# POWER.net
KiCad netlist of a schematic drawn in Altium Designer
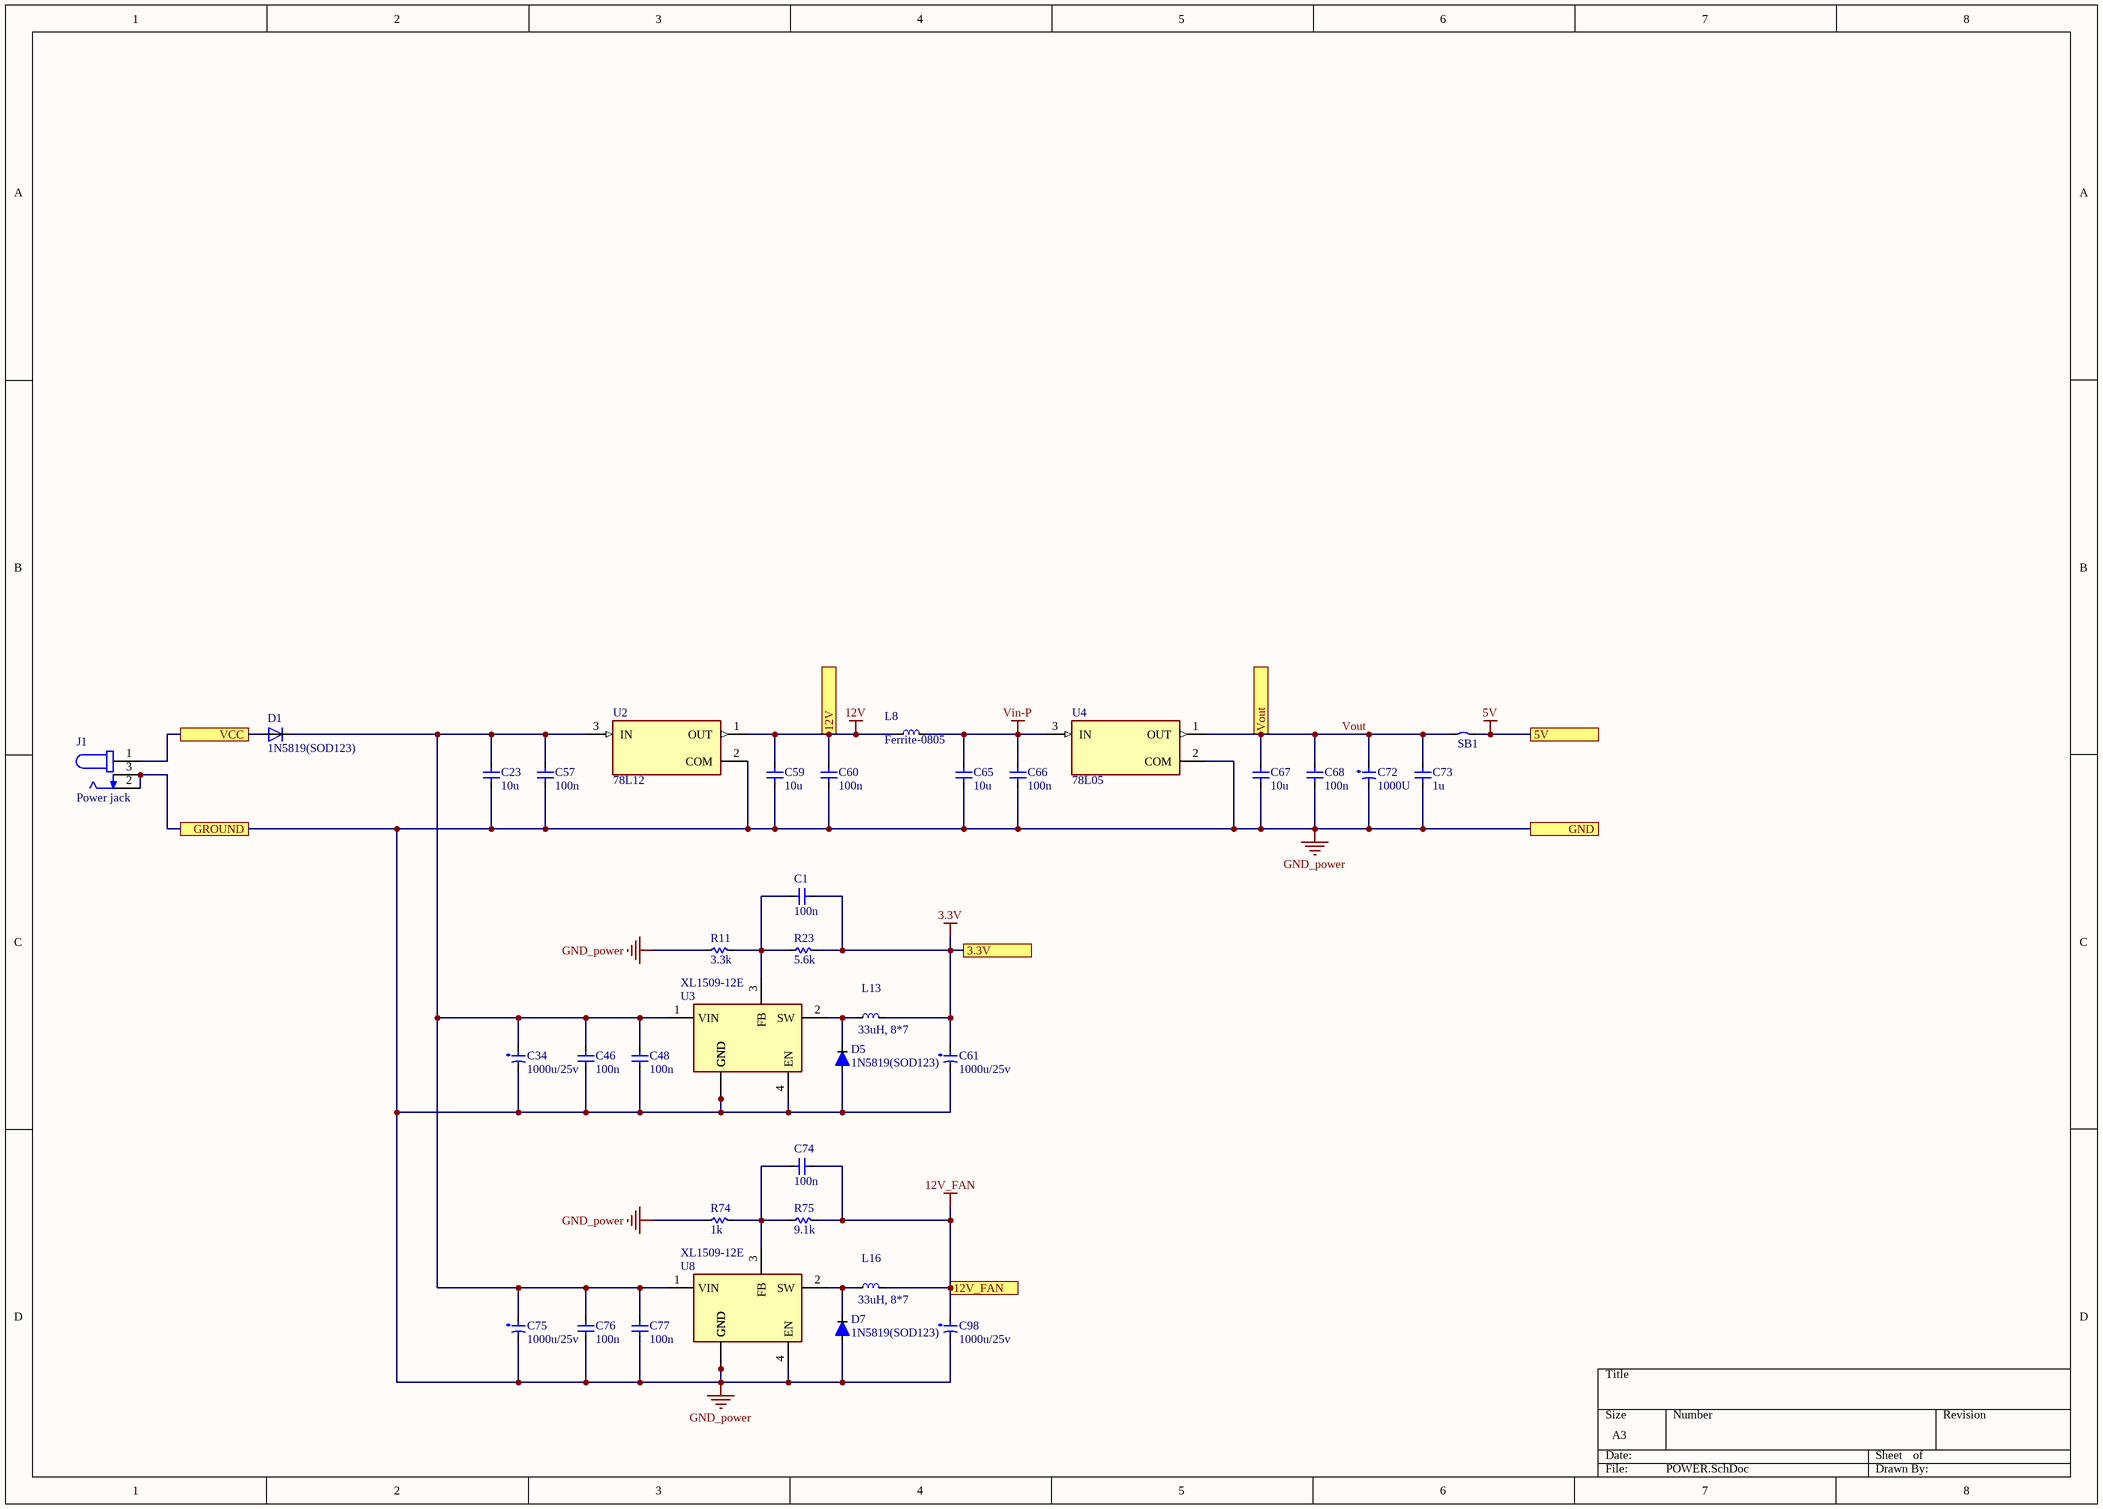
[diagram p0: POWER.SchDoc]

(export (version "E")
  (design (tool "Eeschema 10.0.6"))
  (components
    (comp (ref "C1")
      (value "100n")
      (footprint "cap0603")
      (description "Capacitor 0603")
      (fields (field (name "PUBLISHER") "Altium Limited"))
      (libsource (lib "STM32F103C8T6") (part "Cap 0603"))
    )
    (comp (ref "C23")
      (value "10u")
      (footprint "CAP 0805")
      (description "Capacitor 0805")
      (fields (field (name "PUBLISHER") "Altium Limited"))
      (libsource (lib "Amin-Library") (part "Cap 0805"))
    )
    (comp (ref "C34")
      (value "1000u/25v")
      (footprint "CAP DIP 10*13")
      (description "2200ÂµF 50V Aluminum Electrolytic Capacitors Radial, Can 1000 Hrs @ 105Â°C")
      (fields (field (name "MF") "Nichicon") (field (name "MP") "UVZ1H222MHD"))
      (libsource (lib "mylib1") (part "capacitor dip 10*13"))
    )
    (comp (ref "C46")
      (value "100n")
      (footprint "cap0603")
      (description "Capacitor 0603")
      (fields (field (name "PUBLISHER") "Altium Limited"))
      (libsource (lib "STM32F103C8T6") (part "Cap 0603"))
    )
    (comp (ref "C48")
      (value "100n")
      (footprint "cap0603")
      (description "Capacitor 0603")
      (fields (field (name "PUBLISHER") "Altium Limited"))
      (libsource (lib "STM32F103C8T6") (part "Cap 0603"))
    )
    (comp (ref "C57")
      (value "100n")
      (footprint "cap0603")
      (description "Capacitor 0603")
      (fields (field (name "PUBLISHER") "Altium Limited"))
      (libsource (lib "STM32F103C8T6") (part "Cap 0603"))
    )
    (comp (ref "C59")
      (value "10u")
      (footprint "CAP 0805")
      (description "Capacitor 0805")
      (fields (field (name "PUBLISHER") "Altium Limited"))
      (libsource (lib "Amin-Library") (part "Cap 0805"))
    )
    (comp (ref "C60")
      (value "100n")
      (footprint "cap0603")
      (description "Capacitor 0603")
      (fields (field (name "PUBLISHER") "Altium Limited"))
      (libsource (lib "STM32F103C8T6") (part "Cap 0603"))
    )
    (comp (ref "C61")
      (value "1000u/25v")
      (footprint "CAP DIP 10*13")
      (description "2200ÂµF 50V Aluminum Electrolytic Capacitors Radial, Can 1000 Hrs @ 105Â°C")
      (fields (field (name "MF") "Nichicon") (field (name "MP") "UVZ1H222MHD"))
      (libsource (lib "mylib1") (part "capacitor dip 10*13"))
    )
    (comp (ref "C65")
      (value "10u")
      (footprint "CAP 0805")
      (description "Capacitor 0805")
      (fields (field (name "PUBLISHER") "Altium Limited"))
      (libsource (lib "Amin-Library") (part "Cap 0805"))
    )
    (comp (ref "C66")
      (value "100n")
      (footprint "cap0603")
      (description "Capacitor 0603")
      (fields (field (name "PUBLISHER") "Altium Limited"))
      (libsource (lib "STM32F103C8T6") (part "Cap 0603"))
    )
    (comp (ref "C67")
      (value "10u")
      (footprint "CAP 0805")
      (description "Capacitor 0805")
      (fields (field (name "PUBLISHER") "Altium Limited"))
      (libsource (lib "Amin-Library") (part "Cap 0805"))
    )
    (comp (ref "C68")
      (value "100n")
      (footprint "cap0603")
      (description "Capacitor 0603")
      (fields (field (name "PUBLISHER") "Altium Limited"))
      (libsource (lib "STM32F103C8T6") (part "Cap 0603"))
    )
    (comp (ref "C72")
      (value "1000U")
      (footprint "cap  dip 10*20")
      (description "2200ÂµF 50V Aluminum Electrolytic Capacitors Radial, Can 1000 Hrs @ 105Â°C")
      (fields (field (name "MF") "Nichicon") (field (name "MP") "UVZ1H222MHD"))
      (libsource (lib "Parsa-Library") (part "capacitor dip 10*20"))
    )
    (comp (ref "C73")
      (value "1u")
      (footprint "cap0603")
      (description "Capacitor 0603")
      (fields (field (name "PUBLISHER") "Altium Limited"))
      (libsource (lib "mylib") (part "Cap 0603"))
    )
    (comp (ref "C74")
      (value "100n")
      (footprint "cap0603")
      (description "Capacitor 0603")
      (fields (field (name "PUBLISHER") "Altium Limited"))
      (libsource (lib "STM32F103C8T6") (part "Cap 0603"))
    )
    (comp (ref "C75")
      (value "1000u/25v")
      (footprint "CAP DIP 10*13")
      (description "2200ÂµF 50V Aluminum Electrolytic Capacitors Radial, Can 1000 Hrs @ 105Â°C")
      (fields (field (name "MF") "Nichicon") (field (name "MP") "UVZ1H222MHD"))
      (libsource (lib "mylib1") (part "capacitor dip 10*13"))
    )
    (comp (ref "C76")
      (value "100n")
      (footprint "cap0603")
      (description "Capacitor 0603")
      (fields (field (name "PUBLISHER") "Altium Limited"))
      (libsource (lib "STM32F103C8T6") (part "Cap 0603"))
    )
    (comp (ref "C77")
      (value "100n")
      (footprint "cap0603")
      (description "Capacitor 0603")
      (fields (field (name "PUBLISHER") "Altium Limited"))
      (libsource (lib "STM32F103C8T6") (part "Cap 0603"))
    )
    (comp (ref "C98")
      (value "1000u/25v")
      (footprint "CAP DIP 10*13")
      (description "2200ÂµF 50V Aluminum Electrolytic Capacitors Radial, Can 1000 Hrs @ 105Â°C")
      (fields (field (name "MF") "Nichicon") (field (name "MP") "UVZ1H222MHD"))
      (libsource (lib "mylib1") (part "capacitor dip 10*13"))
    )
    (comp (ref "D1")
      (value "1N5819(SOD123)")
      (footprint "1N5819 SOD-123")
      (description "Shotkey diod SOD-123")
      (fields (field (name "MP") "BAS716") (field (name "MF") "Nexperia USA"))
      (libsource (lib "Amin-Library") (part "1N5819(SOD123)"))
    )
    (comp (ref "D5")
      (value "1N5819(SOD123)")
      (footprint "1N5819 SOD-123")
      (description "Shotkey diod SOD-123")
      (fields (field (name "MP") "BAS716") (field (name "MF") "Nexperia USA"))
      (libsource (lib "") (part "1N5819(SOD123)_1"))
    )
    (comp (ref "D7")
      (value "1N5819(SOD123)")
      (footprint "1N5819 SOD-123")
      (description "Shotkey diod SOD-123")
      (fields (field (name "MP") "BAS716") (field (name "MF") "Nexperia USA"))
      (libsource (lib "") (part "1N5819(SOD123)_1"))
    )
    (comp (ref "J1")
      (value "Power jack")
      (footprint "Power jack")
      (description "2.0 x 6.5 mm, 2.5 A, Horizontal, Through Hole, Tapered Pins, Dc Power Jack Connector")
      (fields (field (name "MF") "CUI Devices") (field (name "MP") "PJ-102A"))
      (libsource (lib "Amin-Library") (part "Power jack"))
    )
    (comp (ref "L8")
      (value "Ferrite-0805")
      (footprint "Ferrite-0805")
      (description "BLM Series 0805 330 Ohm 400 mA 0.58 Ohm DCR Surface Mount Ferrite Bead")
      (fields (field (name "MF") "Murata") (field (name "MP") "BLM18BB331SN1D"))
      (libsource (lib "mylib") (part "Ferrite _0805"))
    )
    (comp (ref "L13")
      (value "33uH, 8*7")
      (footprint "Inductor 8*7")
      (description "Inductor round 8*7")
      (fields (field (name "MP") "DR127-330-R") (field (name "MF") "Eaton"))
      (libsource (lib "Amin-Library") (part "INDUCTOR 8*7"))
    )
    (comp (ref "L16")
      (value "33uH, 8*7")
      (footprint "Inductor 8*7")
      (description "Inductor round 8*7")
      (fields (field (name "MP") "DR127-330-R") (field (name "MF") "Eaton"))
      (libsource (lib "Amin-Library") (part "INDUCTOR 8*7"))
    )
    (comp (ref "R11")
      (value "3.3k")
      (footprint "RES-0603")
      (description "Resistor 0603")
      (fields (field (name "PUBLISHER") "Altium Limited"))
      (libsource (lib "Amin-Library") (part "Res 0603"))
    )
    (comp (ref "R23")
      (value "5.6k")
      (footprint "RES-0603")
      (description "Resistor 0603")
      (fields (field (name "PUBLISHER") "Altium Limited"))
      (libsource (lib "Amin-Library") (part "Res 0603"))
    )
    (comp (ref "R74")
      (value "1k")
      (footprint "RES-0603")
      (description "Resistor 0603")
      (fields (field (name "PUBLISHER") "Altium Limited"))
      (libsource (lib "Amin-Library") (part "Res 0603"))
    )
    (comp (ref "R75")
      (value "9.1k")
      (footprint "RES-0603")
      (description "Resistor 0603")
      (fields (field (name "PUBLISHER") "Altium Limited"))
      (libsource (lib "Amin-Library") (part "Res 0603"))
    )
    (comp (ref "SB1")
      (value "jumper")
      (footprint "JP2_SMD")
      (description "Circuit Breaker")
      (libsource (lib "Amin-Library") (part "jumper"))
    )
    (comp (ref "U2")
      (value "78L12")
      (footprint "78L05")
      (description "Linear Voltage Regulator IC 1 Output 100mA SOT-89-3")
      (fields (field (name "MP") "UA78L05CPK") (field (name "MF") "Texas Instruments"))
      (libsource (lib "Amin-Library") (part "78L05"))
    )
    (comp (ref "U3")
      (value "XL1509-12E")
      (footprint "FR9886")
      (description "Regulator SOP-8")
      (fields (field (name "MANUFACTURER_PART_NUMBER") "FR9886SOGTR"))
      (libsource (lib "Amin-Library") (part "XL1509-12E"))
    )
    (comp (ref "U4")
      (value "78L05")
      (footprint "78L05")
      (description "Linear Voltage Regulator IC 1 Output 100mA SOT-89-3")
      (fields (field (name "MP") "UA78L05CPK") (field (name "MF") "Texas Instruments"))
      (libsource (lib "Amin-Library") (part "78L05"))
    )
    (comp (ref "U8")
      (value "XL1509-12E")
      (footprint "FR9886")
      (description "Regulator SOP-8")
      (fields (field (name "MANUFACTURER_PART_NUMBER") "FR9886SOGTR"))
      (libsource (lib "Amin-Library") (part "XL1509-12E"))
    )
  )
  (nets
    (net (code "1") (name "/VCC") (class "Default")
      (node (ref "D1") (pin "2") (pinfunction "A_2") (pintype "passive"))
      (node (ref "J1") (pin "1") (pinfunction "1_1") (pintype "passive"))
    )
    (net (code "2") (name "/Vout") (class "Default")
      (node (ref "C67") (pin "2") (pinfunction "2_2") (pintype "passive"))
      (node (ref "C68") (pin "2") (pinfunction "2_2") (pintype "passive"))
      (node (ref "C72") (pin "1") (pinfunction "POS_1") (pintype "passive"))
      (node (ref "C73") (pin "2") (pinfunction "2_2") (pintype "passive"))
      (node (ref "SB1") (pin "1") (pinfunction "1_1") (pintype "passive"))
      (node (ref "U4") (pin "1") (pinfunction "OUT_1") (pintype "output"))
    )
    (net (code "3") (name "3.3V") (class "Default")
      (node (ref "C1") (pin "1") (pinfunction "1_1") (pintype "passive"))
      (node (ref "C61") (pin "1") (pinfunction "POS_1") (pintype "passive"))
      (node (ref "L13") (pin "1") (pinfunction "1_1") (pintype "passive"))
      (node (ref "R23") (pin "2") (pinfunction "2_2") (pintype "passive"))
    )
    (net (code "4") (name "5V") (class "Default")
      (node (ref "SB1") (pin "2") (pinfunction "2_2") (pintype "passive"))
    )
    (net (code "5") (name "12V") (class "Default")
      (node (ref "C59") (pin "2") (pinfunction "2_2") (pintype "passive"))
      (node (ref "C60") (pin "2") (pinfunction "2_2") (pintype "passive"))
      (node (ref "L8") (pin "2") (pinfunction "2_2") (pintype "passive"))
      (node (ref "U2") (pin "1") (pinfunction "OUT_1") (pintype "output"))
    )
    (net (code "6") (name "12V_FAN") (class "Default")
      (node (ref "C74") (pin "1") (pinfunction "1_1") (pintype "passive"))
      (node (ref "C98") (pin "1") (pinfunction "POS_1") (pintype "passive"))
      (node (ref "L16") (pin "1") (pinfunction "1_1") (pintype "passive"))
      (node (ref "R75") (pin "2") (pinfunction "2_2") (pintype "passive"))
    )
    (net (code "7") (name "GND_power") (class "Default")
      (node (ref "C23") (pin "1") (pinfunction "1_1") (pintype "passive"))
      (node (ref "C34") (pin "2") (pinfunction "NEG_2") (pintype "passive"))
      (node (ref "C46") (pin "1") (pinfunction "1_1") (pintype "passive"))
      (node (ref "C48") (pin "1") (pinfunction "1_1") (pintype "passive"))
      (node (ref "C57") (pin "1") (pinfunction "1_1") (pintype "passive"))
      (node (ref "C59") (pin "1") (pinfunction "1_1") (pintype "passive"))
      (node (ref "C60") (pin "1") (pinfunction "1_1") (pintype "passive"))
      (node (ref "C61") (pin "2") (pinfunction "NEG_2") (pintype "passive"))
      (node (ref "C65") (pin "1") (pinfunction "1_1") (pintype "passive"))
      (node (ref "C66") (pin "1") (pinfunction "1_1") (pintype "passive"))
      (node (ref "C67") (pin "1") (pinfunction "1_1") (pintype "passive"))
      (node (ref "C68") (pin "1") (pinfunction "1_1") (pintype "passive"))
      (node (ref "C72") (pin "2") (pinfunction "NEG_2") (pintype "passive"))
      (node (ref "C73") (pin "1") (pinfunction "1_1") (pintype "passive"))
      (node (ref "C75") (pin "2") (pinfunction "NEG_2") (pintype "passive"))
      (node (ref "C76") (pin "1") (pinfunction "1_1") (pintype "passive"))
      (node (ref "C77") (pin "1") (pinfunction "1_1") (pintype "passive"))
      (node (ref "C98") (pin "2") (pinfunction "NEG_2") (pintype "passive"))
      (node (ref "D5") (pin "2") (pinfunction "C_2") (pintype "passive"))
      (node (ref "D7") (pin "2") (pinfunction "C_2") (pintype "passive"))
      (node (ref "J1") (pin "2") (pinfunction "2_2") (pintype "passive"))
      (node (ref "J1") (pin "3") (pinfunction "3_3") (pintype "passive"))
      (node (ref "R11") (pin "1") (pinfunction "1_1") (pintype "passive"))
      (node (ref "R74") (pin "1") (pinfunction "1_1") (pintype "passive"))
      (node (ref "U2") (pin "2") (pinfunction "COM_2") (pintype "power_in"))
      (node (ref "U3") (pin "4") (pinfunction "EN_4") (pintype "passive"))
      (node (ref "U3") (pin "5") (pinfunction "GND_5") (pintype "passive"))
      (node (ref "U3") (pin "6") (pinfunction "GND_6") (pintype "passive"))
      (node (ref "U3") (pin "7") (pinfunction "GND_7") (pintype "passive"))
      (node (ref "U3") (pin "8") (pinfunction "GND_8") (pintype "passive"))
      (node (ref "U4") (pin "2") (pinfunction "COM_2") (pintype "power_in"))
      (node (ref "U8") (pin "4") (pinfunction "EN_4") (pintype "passive"))
      (node (ref "U8") (pin "5") (pinfunction "GND_5") (pintype "passive"))
      (node (ref "U8") (pin "6") (pinfunction "GND_6") (pintype "passive"))
      (node (ref "U8") (pin "7") (pinfunction "GND_7") (pintype "passive"))
      (node (ref "U8") (pin "8") (pinfunction "GND_8") (pintype "passive"))
    )
    (net (code "8") (name "Net-(C34-POS)") (class "Default")
      (node (ref "C23") (pin "2") (pinfunction "2_2") (pintype "passive"))
      (node (ref "C34") (pin "1") (pinfunction "POS_1") (pintype "passive"))
      (node (ref "C46") (pin "2") (pinfunction "2_2") (pintype "passive"))
      (node (ref "C48") (pin "2") (pinfunction "2_2") (pintype "passive"))
      (node (ref "C57") (pin "2") (pinfunction "2_2") (pintype "passive"))
      (node (ref "C75") (pin "1") (pinfunction "POS_1") (pintype "passive"))
      (node (ref "C76") (pin "2") (pinfunction "2_2") (pintype "passive"))
      (node (ref "C77") (pin "2") (pinfunction "2_2") (pintype "passive"))
      (node (ref "D1") (pin "1") (pinfunction "K_1") (pintype "passive"))
      (node (ref "U2") (pin "3") (pinfunction "IN_3") (pintype "input"))
      (node (ref "U3") (pin "1") (pinfunction "VIN_1") (pintype "passive"))
      (node (ref "U8") (pin "1") (pinfunction "VIN_1") (pintype "passive"))
    )
    (net (code "9") (name "Net-(D5-A)") (class "Default")
      (node (ref "D5") (pin "1") (pinfunction "A_1") (pintype "passive"))
      (node (ref "L13") (pin "2") (pinfunction "2_2") (pintype "passive"))
      (node (ref "U3") (pin "2") (pinfunction "SW_2") (pintype "passive"))
    )
    (net (code "10") (name "Net-(D7-A)") (class "Default")
      (node (ref "D7") (pin "1") (pinfunction "A_1") (pintype "passive"))
      (node (ref "L16") (pin "2") (pinfunction "2_2") (pintype "passive"))
      (node (ref "U8") (pin "2") (pinfunction "SW_2") (pintype "passive"))
    )
    (net (code "11") (name "Net-(U3-FB)") (class "Default")
      (node (ref "C1") (pin "2") (pinfunction "2_2") (pintype "passive"))
      (node (ref "R11") (pin "2") (pinfunction "2_2") (pintype "passive"))
      (node (ref "R23") (pin "1") (pinfunction "1_1") (pintype "passive"))
      (node (ref "U3") (pin "3") (pinfunction "FB_3") (pintype "passive"))
    )
    (net (code "12") (name "Net-(U8-FB)") (class "Default")
      (node (ref "C74") (pin "2") (pinfunction "2_2") (pintype "passive"))
      (node (ref "R74") (pin "2") (pinfunction "2_2") (pintype "passive"))
      (node (ref "R75") (pin "1") (pinfunction "1_1") (pintype "passive"))
      (node (ref "U8") (pin "3") (pinfunction "FB_3") (pintype "passive"))
    )
    (net (code "13") (name "Vin-P") (class "Default")
      (node (ref "C65") (pin "2") (pinfunction "2_2") (pintype "passive"))
      (node (ref "C66") (pin "2") (pinfunction "2_2") (pintype "passive"))
      (node (ref "L8") (pin "1") (pinfunction "1_1") (pintype "passive"))
      (node (ref "U4") (pin "3") (pinfunction "IN_3") (pintype "input"))
    )
  )
)
